# teensyShield1_0.net
KiCad netlist of a schematic drawn in EAGLE
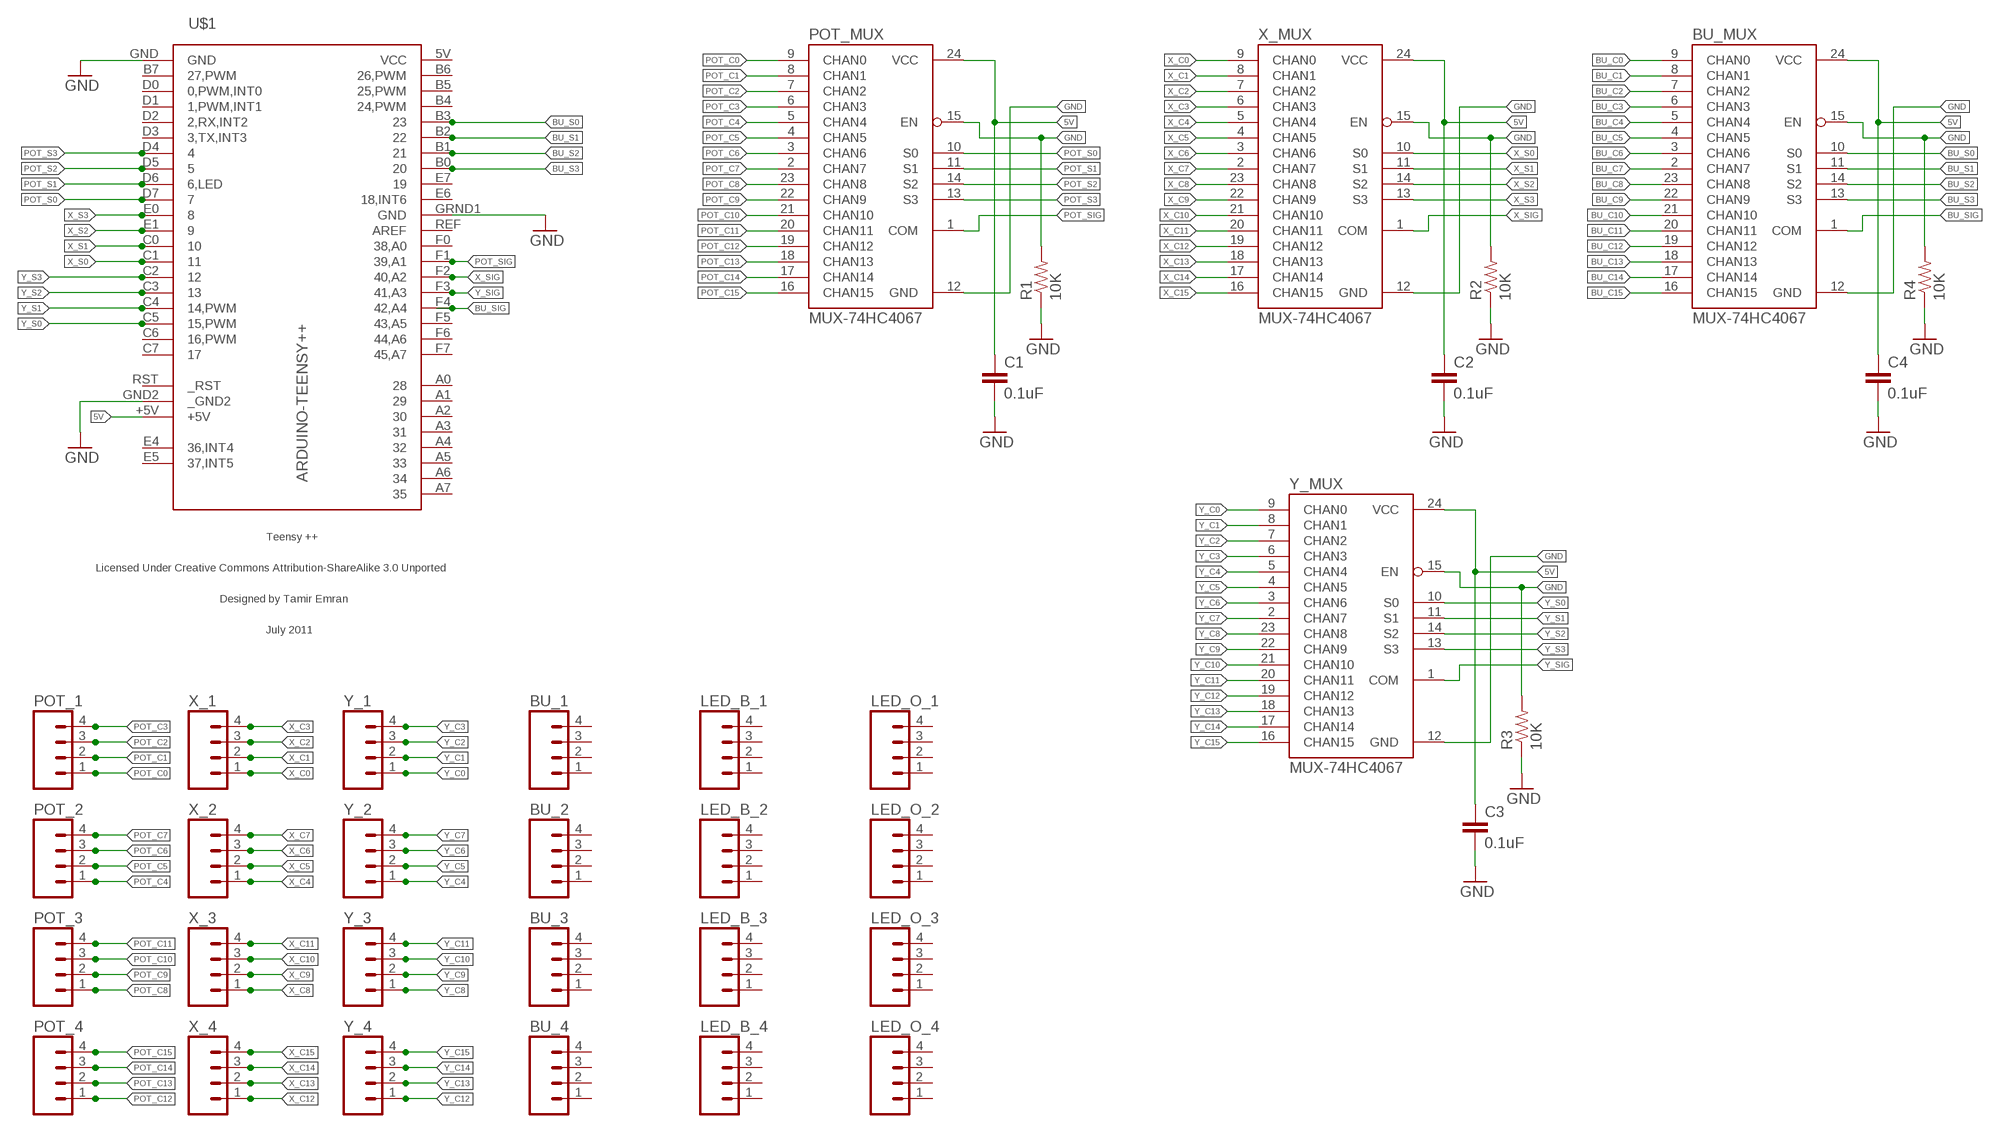
[diagram p0: schematic, sheet 1]

(export (version "E")
  (design (tool "Eeschema 10.0.6"))
  (components
    (comp (ref "BU_1")
      (value "M04NO_SILK_ALL_ROUND")
      (footprint "eagle-import:1X04_NO_SILK_ALL_ROUND")
      (libsource (lib "eagle-import") (part "M04NO_SILK_ALL_ROUND"))
    )
    (comp (ref "BU_2")
      (value "M04NO_SILK_ALL_ROUND")
      (footprint "eagle-import:1X04_NO_SILK_ALL_ROUND")
      (libsource (lib "eagle-import") (part "M04NO_SILK_ALL_ROUND"))
    )
    (comp (ref "BU_3")
      (value "M04NO_SILK_ALL_ROUND")
      (footprint "eagle-import:1X04_NO_SILK_ALL_ROUND")
      (libsource (lib "eagle-import") (part "M04NO_SILK_ALL_ROUND"))
    )
    (comp (ref "BU_4")
      (value "M04NO_SILK_ALL_ROUND")
      (footprint "eagle-import:1X04_NO_SILK_ALL_ROUND")
      (libsource (lib "eagle-import") (part "M04NO_SILK_ALL_ROUND"))
    )
    (comp (ref "BU_MUX")
      (value "MUX-74HC4067")
      (footprint "eagle-import:SSOP24")
      (libsource (lib "eagle-import") (part "MUX-74HC4067SMD"))
    )
    (comp (ref "C1")
      (value "0.1uF")
      (footprint "eagle-import:0603")
      (libsource (lib "eagle-import") (part "CAP0603"))
    )
    (comp (ref "C2")
      (value "0.1uF")
      (footprint "eagle-import:0603")
      (libsource (lib "eagle-import") (part "CAP0603"))
    )
    (comp (ref "C3")
      (value "0.1uF")
      (footprint "eagle-import:0603")
      (libsource (lib "eagle-import") (part "CAP0603"))
    )
    (comp (ref "C4")
      (value "0.1uF")
      (footprint "eagle-import:0603")
      (libsource (lib "eagle-import") (part "CAP0603"))
    )
    (comp (ref "LED_B_1")
      (value "M04NO_SILK_ALL_ROUND")
      (footprint "eagle-import:1X04_NO_SILK_ALL_ROUND")
      (libsource (lib "eagle-import") (part "M04NO_SILK_ALL_ROUND"))
    )
    (comp (ref "LED_B_2")
      (value "M04NO_SILK_ALL_ROUND")
      (footprint "eagle-import:1X04_NO_SILK_ALL_ROUND")
      (libsource (lib "eagle-import") (part "M04NO_SILK_ALL_ROUND"))
    )
    (comp (ref "LED_B_3")
      (value "M04NO_SILK_ALL_ROUND")
      (footprint "eagle-import:1X04_NO_SILK_ALL_ROUND")
      (libsource (lib "eagle-import") (part "M04NO_SILK_ALL_ROUND"))
    )
    (comp (ref "LED_B_4")
      (value "M04NO_SILK_ALL_ROUND")
      (footprint "eagle-import:1X04_NO_SILK_ALL_ROUND")
      (libsource (lib "eagle-import") (part "M04NO_SILK_ALL_ROUND"))
    )
    (comp (ref "LED_O_1")
      (value "M04NO_SILK_ALL_ROUND")
      (footprint "eagle-import:1X04_NO_SILK_ALL_ROUND")
      (libsource (lib "eagle-import") (part "M04NO_SILK_ALL_ROUND"))
    )
    (comp (ref "LED_O_2")
      (value "M04NO_SILK_ALL_ROUND")
      (footprint "eagle-import:1X04_NO_SILK_ALL_ROUND")
      (libsource (lib "eagle-import") (part "M04NO_SILK_ALL_ROUND"))
    )
    (comp (ref "LED_O_3")
      (value "M04NO_SILK_ALL_ROUND")
      (footprint "eagle-import:1X04_NO_SILK_ALL_ROUND")
      (libsource (lib "eagle-import") (part "M04NO_SILK_ALL_ROUND"))
    )
    (comp (ref "LED_O_4")
      (value "M04NO_SILK_ALL_ROUND")
      (footprint "eagle-import:1X04_NO_SILK_ALL_ROUND")
      (libsource (lib "eagle-import") (part "M04NO_SILK_ALL_ROUND"))
    )
    (comp (ref "POT_1")
      (value "M04NO_SILK_ALL_ROUND")
      (footprint "eagle-import:1X04_NO_SILK_ALL_ROUND")
      (libsource (lib "eagle-import") (part "M04NO_SILK_ALL_ROUND"))
    )
    (comp (ref "POT_2")
      (value "M04NO_SILK_ALL_ROUND")
      (footprint "eagle-import:1X04_NO_SILK_ALL_ROUND")
      (libsource (lib "eagle-import") (part "M04NO_SILK_ALL_ROUND"))
    )
    (comp (ref "POT_3")
      (value "M04NO_SILK_ALL_ROUND")
      (footprint "eagle-import:1X04_NO_SILK_ALL_ROUND")
      (libsource (lib "eagle-import") (part "M04NO_SILK_ALL_ROUND"))
    )
    (comp (ref "POT_4")
      (value "M04NO_SILK_ALL_ROUND")
      (footprint "eagle-import:1X04_NO_SILK_ALL_ROUND")
      (libsource (lib "eagle-import") (part "M04NO_SILK_ALL_ROUND"))
    )
    (comp (ref "POT_MUX")
      (value "MUX-74HC4067")
      (footprint "eagle-import:SSOP24")
      (libsource (lib "eagle-import") (part "MUX-74HC4067SMD"))
    )
    (comp (ref "R1")
      (value "10K")
      (footprint "eagle-import:0603")
      (libsource (lib "eagle-import") (part "RESISTOR0603"))
    )
    (comp (ref "R2")
      (value "10K")
      (footprint "eagle-import:0603")
      (libsource (lib "eagle-import") (part "RESISTOR0603"))
    )
    (comp (ref "R3")
      (value "10K")
      (footprint "eagle-import:0603")
      (libsource (lib "eagle-import") (part "RESISTOR0603"))
    )
    (comp (ref "R4")
      (value "10K")
      (footprint "eagle-import:0603")
      (libsource (lib "eagle-import") (part "RESISTOR0603"))
    )
    (comp (ref "U$1")
      (value "ARDUINO-TEENSY++")
      (footprint "eagle-import:TEENSY++")
      (libsource (lib "eagle-import") (part "ARDUINO-TEENSY++"))
    )
    (comp (ref "X_1")
      (value "M04NO_SILK_ALL_ROUND")
      (footprint "eagle-import:1X04_NO_SILK_ALL_ROUND")
      (libsource (lib "eagle-import") (part "M04NO_SILK_ALL_ROUND"))
    )
    (comp (ref "X_2")
      (value "M04NO_SILK_ALL_ROUND")
      (footprint "eagle-import:1X04_NO_SILK_ALL_ROUND")
      (libsource (lib "eagle-import") (part "M04NO_SILK_ALL_ROUND"))
    )
    (comp (ref "X_3")
      (value "M04NO_SILK_ALL_ROUND")
      (footprint "eagle-import:1X04_NO_SILK_ALL_ROUND")
      (libsource (lib "eagle-import") (part "M04NO_SILK_ALL_ROUND"))
    )
    (comp (ref "X_4")
      (value "M04NO_SILK_ALL_ROUND")
      (footprint "eagle-import:1X04_NO_SILK_ALL_ROUND")
      (libsource (lib "eagle-import") (part "M04NO_SILK_ALL_ROUND"))
    )
    (comp (ref "X_MUX")
      (value "MUX-74HC4067")
      (footprint "eagle-import:SSOP24")
      (libsource (lib "eagle-import") (part "MUX-74HC4067SMD"))
    )
    (comp (ref "Y_1")
      (value "M04NO_SILK_ALL_ROUND")
      (footprint "eagle-import:1X04_NO_SILK_ALL_ROUND")
      (libsource (lib "eagle-import") (part "M04NO_SILK_ALL_ROUND"))
    )
    (comp (ref "Y_2")
      (value "M04NO_SILK_ALL_ROUND")
      (footprint "eagle-import:1X04_NO_SILK_ALL_ROUND")
      (libsource (lib "eagle-import") (part "M04NO_SILK_ALL_ROUND"))
    )
    (comp (ref "Y_3")
      (value "M04NO_SILK_ALL_ROUND")
      (footprint "eagle-import:1X04_NO_SILK_ALL_ROUND")
      (libsource (lib "eagle-import") (part "M04NO_SILK_ALL_ROUND"))
    )
    (comp (ref "Y_4")
      (value "M04NO_SILK_ALL_ROUND")
      (footprint "eagle-import:1X04_NO_SILK_ALL_ROUND")
      (libsource (lib "eagle-import") (part "M04NO_SILK_ALL_ROUND"))
    )
    (comp (ref "Y_MUX")
      (value "MUX-74HC4067")
      (footprint "eagle-import:SSOP24")
      (libsource (lib "eagle-import") (part "MUX-74HC4067SMD"))
    )
  )
  (nets
    (net (code "1") (name "/VCC") (class "Default")
      (node (ref "U$1") (pin "5V") (pinfunction "VCC_5V") (pintype "power_in"))
    )
    (net (code "2") (name "5V") (class "Default")
      (node (ref "BU_MUX") (pin "24") (pinfunction "VCC_24") (pintype "bidirectional"))
      (node (ref "C1") (pin "1") (pinfunction "1_1") (pintype "passive"))
      (node (ref "C2") (pin "1") (pinfunction "1_1") (pintype "passive"))
      (node (ref "C3") (pin "1") (pinfunction "1_1") (pintype "passive"))
      (node (ref "C4") (pin "1") (pinfunction "1_1") (pintype "passive"))
      (node (ref "POT_MUX") (pin "24") (pinfunction "VCC_24") (pintype "bidirectional"))
      (node (ref "X_MUX") (pin "24") (pinfunction "VCC_24") (pintype "bidirectional"))
      (node (ref "Y_MUX") (pin "24") (pinfunction "VCC_24") (pintype "bidirectional"))
    )
    (net (code "3") (name "BU_C0") (class "Default")
      (node (ref "BU_MUX") (pin "9") (pinfunction "CHAN0_9") (pintype "bidirectional"))
    )
    (net (code "4") (name "BU_C1") (class "Default")
      (node (ref "BU_MUX") (pin "8") (pinfunction "CHAN1_8") (pintype "bidirectional"))
    )
    (net (code "5") (name "BU_C2") (class "Default")
      (node (ref "BU_MUX") (pin "7") (pinfunction "CHAN2_7") (pintype "bidirectional"))
    )
    (net (code "6") (name "BU_C3") (class "Default")
      (node (ref "BU_MUX") (pin "6") (pinfunction "CHAN3_6") (pintype "bidirectional"))
    )
    (net (code "7") (name "BU_C4") (class "Default")
      (node (ref "BU_MUX") (pin "5") (pinfunction "CHAN4_5") (pintype "bidirectional"))
    )
    (net (code "8") (name "BU_C5") (class "Default")
      (node (ref "BU_MUX") (pin "4") (pinfunction "CHAN5_4") (pintype "bidirectional"))
    )
    (net (code "9") (name "BU_C6") (class "Default")
      (node (ref "BU_MUX") (pin "3") (pinfunction "CHAN6_3") (pintype "bidirectional"))
    )
    (net (code "10") (name "BU_C7") (class "Default")
      (node (ref "BU_MUX") (pin "2") (pinfunction "CHAN7_2") (pintype "bidirectional"))
    )
    (net (code "11") (name "BU_C8") (class "Default")
      (node (ref "BU_MUX") (pin "23") (pinfunction "CHAN8_23") (pintype "bidirectional"))
    )
    (net (code "12") (name "BU_C9") (class "Default")
      (node (ref "BU_MUX") (pin "22") (pinfunction "CHAN9_22") (pintype "bidirectional"))
    )
    (net (code "13") (name "BU_C10") (class "Default")
      (node (ref "BU_MUX") (pin "21") (pinfunction "CHAN10_21") (pintype "bidirectional"))
    )
    (net (code "14") (name "BU_C11") (class "Default")
      (node (ref "BU_MUX") (pin "20") (pinfunction "CHAN11_20") (pintype "bidirectional"))
    )
    (net (code "15") (name "BU_C12") (class "Default")
      (node (ref "BU_MUX") (pin "19") (pinfunction "CHAN12_19") (pintype "bidirectional"))
    )
    (net (code "16") (name "BU_C13") (class "Default")
      (node (ref "BU_MUX") (pin "18") (pinfunction "CHAN13_18") (pintype "bidirectional"))
    )
    (net (code "17") (name "BU_C14") (class "Default")
      (node (ref "BU_MUX") (pin "17") (pinfunction "CHAN14_17") (pintype "bidirectional"))
    )
    (net (code "18") (name "BU_C15") (class "Default")
      (node (ref "BU_MUX") (pin "16") (pinfunction "CHAN15_16") (pintype "bidirectional"))
    )
    (net (code "19") (name "BU_S0") (class "Default")
      (node (ref "BU_MUX") (pin "10") (pinfunction "S0_10") (pintype "input"))
      (node (ref "U$1") (pin "B3") (pinfunction "23_B3") (pintype "bidirectional"))
    )
    (net (code "20") (name "BU_S1") (class "Default")
      (node (ref "BU_MUX") (pin "11") (pinfunction "S1_11") (pintype "input"))
      (node (ref "U$1") (pin "B2") (pinfunction "22_B2") (pintype "bidirectional"))
    )
    (net (code "21") (name "BU_S2") (class "Default")
      (node (ref "BU_MUX") (pin "14") (pinfunction "S2_14") (pintype "input"))
      (node (ref "U$1") (pin "B1") (pinfunction "21_B1") (pintype "bidirectional"))
    )
    (net (code "22") (name "BU_S3") (class "Default")
      (node (ref "BU_MUX") (pin "13") (pinfunction "S3_13") (pintype "input"))
      (node (ref "U$1") (pin "B0") (pinfunction "20_B0") (pintype "bidirectional"))
    )
    (net (code "23") (name "BU_SIG") (class "Default")
      (node (ref "BU_MUX") (pin "1") (pinfunction "COM_1") (pintype "bidirectional"))
      (node (ref "U$1") (pin "F4") (pinfunction "42,A4_F4") (pintype "bidirectional"))
    )
    (net (code "24") (name "GND") (class "Default")
      (node (ref "BU_MUX") (pin "12") (pinfunction "GND_12") (pintype "bidirectional"))
      (node (ref "BU_MUX") (pin "15") (pinfunction "EN_15") (pintype "input"))
      (node (ref "C1") (pin "2") (pinfunction "2_2") (pintype "passive"))
      (node (ref "C2") (pin "2") (pinfunction "2_2") (pintype "passive"))
      (node (ref "C3") (pin "2") (pinfunction "2_2") (pintype "passive"))
      (node (ref "C4") (pin "2") (pinfunction "2_2") (pintype "passive"))
      (node (ref "POT_MUX") (pin "12") (pinfunction "GND_12") (pintype "bidirectional"))
      (node (ref "POT_MUX") (pin "15") (pinfunction "EN_15") (pintype "input"))
      (node (ref "R1") (pin "1") (pinfunction "1_1") (pintype "passive"))
      (node (ref "R1") (pin "2") (pinfunction "2_2") (pintype "passive"))
      (node (ref "R2") (pin "1") (pinfunction "1_1") (pintype "passive"))
      (node (ref "R2") (pin "2") (pinfunction "2_2") (pintype "passive"))
      (node (ref "R3") (pin "1") (pinfunction "1_1") (pintype "passive"))
      (node (ref "R3") (pin "2") (pinfunction "2_2") (pintype "passive"))
      (node (ref "R4") (pin "1") (pinfunction "1_1") (pintype "passive"))
      (node (ref "R4") (pin "2") (pinfunction "2_2") (pintype "passive"))
      (node (ref "U$1") (pin "GND") (pinfunction "GND_GND") (pintype "power_in"))
      (node (ref "U$1") (pin "GND2") (pinfunction "_GND2_GND2") (pintype "power_in"))
      (node (ref "U$1") (pin "GRND1") (pinfunction "GND_GRND1") (pintype "power_in"))
      (node (ref "X_MUX") (pin "12") (pinfunction "GND_12") (pintype "bidirectional"))
      (node (ref "X_MUX") (pin "15") (pinfunction "EN_15") (pintype "input"))
      (node (ref "Y_MUX") (pin "12") (pinfunction "GND_12") (pintype "bidirectional"))
      (node (ref "Y_MUX") (pin "15") (pinfunction "EN_15") (pintype "input"))
    )
    (net (code "25") (name "POT_C0") (class "Default")
      (node (ref "POT_1") (pin "1") (pinfunction "1_1") (pintype "passive"))
      (node (ref "POT_MUX") (pin "9") (pinfunction "CHAN0_9") (pintype "bidirectional"))
    )
    (net (code "26") (name "POT_C1") (class "Default")
      (node (ref "POT_1") (pin "2") (pinfunction "2_2") (pintype "passive"))
      (node (ref "POT_MUX") (pin "8") (pinfunction "CHAN1_8") (pintype "bidirectional"))
    )
    (net (code "27") (name "POT_C2") (class "Default")
      (node (ref "POT_1") (pin "3") (pinfunction "3_3") (pintype "passive"))
      (node (ref "POT_MUX") (pin "7") (pinfunction "CHAN2_7") (pintype "bidirectional"))
    )
    (net (code "28") (name "POT_C3") (class "Default")
      (node (ref "POT_1") (pin "4") (pinfunction "4_4") (pintype "passive"))
      (node (ref "POT_MUX") (pin "6") (pinfunction "CHAN3_6") (pintype "bidirectional"))
    )
    (net (code "29") (name "POT_C4") (class "Default")
      (node (ref "POT_2") (pin "1") (pinfunction "1_1") (pintype "passive"))
      (node (ref "POT_MUX") (pin "5") (pinfunction "CHAN4_5") (pintype "bidirectional"))
    )
    (net (code "30") (name "POT_C5") (class "Default")
      (node (ref "POT_2") (pin "2") (pinfunction "2_2") (pintype "passive"))
      (node (ref "POT_MUX") (pin "4") (pinfunction "CHAN5_4") (pintype "bidirectional"))
    )
    (net (code "31") (name "POT_C6") (class "Default")
      (node (ref "POT_2") (pin "3") (pinfunction "3_3") (pintype "passive"))
      (node (ref "POT_MUX") (pin "3") (pinfunction "CHAN6_3") (pintype "bidirectional"))
    )
    (net (code "32") (name "POT_C7") (class "Default")
      (node (ref "POT_2") (pin "4") (pinfunction "4_4") (pintype "passive"))
      (node (ref "POT_MUX") (pin "2") (pinfunction "CHAN7_2") (pintype "bidirectional"))
    )
    (net (code "33") (name "POT_C8") (class "Default")
      (node (ref "POT_3") (pin "1") (pinfunction "1_1") (pintype "passive"))
      (node (ref "POT_MUX") (pin "23") (pinfunction "CHAN8_23") (pintype "bidirectional"))
    )
    (net (code "34") (name "POT_C9") (class "Default")
      (node (ref "POT_3") (pin "2") (pinfunction "2_2") (pintype "passive"))
      (node (ref "POT_MUX") (pin "22") (pinfunction "CHAN9_22") (pintype "bidirectional"))
    )
    (net (code "35") (name "POT_C10") (class "Default")
      (node (ref "POT_3") (pin "3") (pinfunction "3_3") (pintype "passive"))
      (node (ref "POT_MUX") (pin "21") (pinfunction "CHAN10_21") (pintype "bidirectional"))
    )
    (net (code "36") (name "POT_C11") (class "Default")
      (node (ref "POT_3") (pin "4") (pinfunction "4_4") (pintype "passive"))
      (node (ref "POT_MUX") (pin "20") (pinfunction "CHAN11_20") (pintype "bidirectional"))
    )
    (net (code "37") (name "POT_C12") (class "Default")
      (node (ref "POT_4") (pin "1") (pinfunction "1_1") (pintype "passive"))
      (node (ref "POT_MUX") (pin "19") (pinfunction "CHAN12_19") (pintype "bidirectional"))
    )
    (net (code "38") (name "POT_C13") (class "Default")
      (node (ref "POT_4") (pin "2") (pinfunction "2_2") (pintype "passive"))
      (node (ref "POT_MUX") (pin "18") (pinfunction "CHAN13_18") (pintype "bidirectional"))
    )
    (net (code "39") (name "POT_C14") (class "Default")
      (node (ref "POT_4") (pin "3") (pinfunction "3_3") (pintype "passive"))
      (node (ref "POT_MUX") (pin "17") (pinfunction "CHAN14_17") (pintype "bidirectional"))
    )
    (net (code "40") (name "POT_C15") (class "Default")
      (node (ref "POT_4") (pin "4") (pinfunction "4_4") (pintype "passive"))
      (node (ref "POT_MUX") (pin "16") (pinfunction "CHAN15_16") (pintype "bidirectional"))
    )
    (net (code "41") (name "POT_S0") (class "Default")
      (node (ref "POT_MUX") (pin "10") (pinfunction "S0_10") (pintype "input"))
      (node (ref "U$1") (pin "D7") (pinfunction "7_D7") (pintype "bidirectional"))
    )
    (net (code "42") (name "POT_S1") (class "Default")
      (node (ref "POT_MUX") (pin "11") (pinfunction "S1_11") (pintype "input"))
      (node (ref "U$1") (pin "D6") (pinfunction "6,LED_D6") (pintype "bidirectional"))
    )
    (net (code "43") (name "POT_S2") (class "Default")
      (node (ref "POT_MUX") (pin "14") (pinfunction "S2_14") (pintype "input"))
      (node (ref "U$1") (pin "D5") (pinfunction "5_D5") (pintype "bidirectional"))
    )
    (net (code "44") (name "POT_S3") (class "Default")
      (node (ref "POT_MUX") (pin "13") (pinfunction "S3_13") (pintype "input"))
      (node (ref "U$1") (pin "D4") (pinfunction "4_D4") (pintype "bidirectional"))
    )
    (net (code "45") (name "POT_SIG") (class "Default")
      (node (ref "POT_MUX") (pin "1") (pinfunction "COM_1") (pintype "bidirectional"))
    )
    (net (code "46") (name "X_C0") (class "Default")
      (node (ref "X_1") (pin "1") (pinfunction "1_1") (pintype "passive"))
      (node (ref "X_MUX") (pin "9") (pinfunction "CHAN0_9") (pintype "bidirectional"))
    )
    (net (code "47") (name "X_C1") (class "Default")
      (node (ref "X_1") (pin "2") (pinfunction "2_2") (pintype "passive"))
      (node (ref "X_MUX") (pin "8") (pinfunction "CHAN1_8") (pintype "bidirectional"))
    )
    (net (code "48") (name "X_C2") (class "Default")
      (node (ref "X_1") (pin "3") (pinfunction "3_3") (pintype "passive"))
      (node (ref "X_MUX") (pin "7") (pinfunction "CHAN2_7") (pintype "bidirectional"))
    )
    (net (code "49") (name "X_C3") (class "Default")
      (node (ref "X_1") (pin "4") (pinfunction "4_4") (pintype "passive"))
      (node (ref "X_MUX") (pin "6") (pinfunction "CHAN3_6") (pintype "bidirectional"))
    )
    (net (code "50") (name "X_C4") (class "Default")
      (node (ref "X_2") (pin "1") (pinfunction "1_1") (pintype "passive"))
      (node (ref "X_MUX") (pin "5") (pinfunction "CHAN4_5") (pintype "bidirectional"))
    )
    (net (code "51") (name "X_C5") (class "Default")
      (node (ref "X_2") (pin "2") (pinfunction "2_2") (pintype "passive"))
      (node (ref "X_MUX") (pin "4") (pinfunction "CHAN5_4") (pintype "bidirectional"))
    )
    (net (code "52") (name "X_C6") (class "Default")
      (node (ref "X_2") (pin "3") (pinfunction "3_3") (pintype "passive"))
      (node (ref "X_MUX") (pin "3") (pinfunction "CHAN6_3") (pintype "bidirectional"))
    )
    (net (code "53") (name "X_C7") (class "Default")
      (node (ref "X_2") (pin "4") (pinfunction "4_4") (pintype "passive"))
      (node (ref "X_MUX") (pin "2") (pinfunction "CHAN7_2") (pintype "bidirectional"))
    )
    (net (code "54") (name "X_C8") (class "Default")
      (node (ref "X_3") (pin "1") (pinfunction "1_1") (pintype "passive"))
      (node (ref "X_MUX") (pin "23") (pinfunction "CHAN8_23") (pintype "bidirectional"))
    )
    (net (code "55") (name "X_C9") (class "Default")
      (node (ref "X_3") (pin "2") (pinfunction "2_2") (pintype "passive"))
      (node (ref "X_MUX") (pin "22") (pinfunction "CHAN9_22") (pintype "bidirectional"))
    )
    (net (code "56") (name "X_C10") (class "Default")
      (node (ref "X_3") (pin "3") (pinfunction "3_3") (pintype "passive"))
      (node (ref "X_MUX") (pin "21") (pinfunction "CHAN10_21") (pintype "bidirectional"))
    )
    (net (code "57") (name "X_C11") (class "Default")
      (node (ref "X_3") (pin "4") (pinfunction "4_4") (pintype "passive"))
      (node (ref "X_MUX") (pin "20") (pinfunction "CHAN11_20") (pintype "bidirectional"))
    )
    (net (code "58") (name "X_C12") (class "Default")
      (node (ref "X_4") (pin "1") (pinfunction "1_1") (pintype "passive"))
      (node (ref "X_MUX") (pin "19") (pinfunction "CHAN12_19") (pintype "bidirectional"))
    )
    (net (code "59") (name "X_C13") (class "Default")
      (node (ref "X_4") (pin "2") (pinfunction "2_2") (pintype "passive"))
      (node (ref "X_MUX") (pin "18") (pinfunction "CHAN13_18") (pintype "bidirectional"))
    )
    (net (code "60") (name "X_C14") (class "Default")
      (node (ref "X_4") (pin "3") (pinfunction "3_3") (pintype "passive"))
      (node (ref "X_MUX") (pin "17") (pinfunction "CHAN14_17") (pintype "bidirectional"))
    )
    (net (code "61") (name "X_C15") (class "Default")
      (node (ref "X_4") (pin "4") (pinfunction "4_4") (pintype "passive"))
      (node (ref "X_MUX") (pin "16") (pinfunction "CHAN15_16") (pintype "bidirectional"))
    )
    (net (code "62") (name "X_S0") (class "Default")
      (node (ref "U$1") (pin "C1") (pinfunction "11_C1") (pintype "bidirectional"))
      (node (ref "X_MUX") (pin "10") (pinfunction "S0_10") (pintype "input"))
    )
    (net (code "63") (name "X_S1") (class "Default")
      (node (ref "U$1") (pin "C0") (pinfunction "10_C0") (pintype "bidirectional"))
      (node (ref "X_MUX") (pin "11") (pinfunction "S1_11") (pintype "input"))
    )
    (net (code "64") (name "X_S2") (class "Default")
      (node (ref "U$1") (pin "E1") (pinfunction "9_E1") (pintype "bidirectional"))
      (node (ref "X_MUX") (pin "14") (pinfunction "S2_14") (pintype "input"))
    )
    (net (code "65") (name "X_S3") (class "Default")
      (node (ref "U$1") (pin "E0") (pinfunction "8_E0") (pintype "bidirectional"))
      (node (ref "X_MUX") (pin "13") (pinfunction "S3_13") (pintype "input"))
    )
    (net (code "66") (name "X_SIG") (class "Default")
      (node (ref "X_MUX") (pin "1") (pinfunction "COM_1") (pintype "bidirectional"))
    )
    (net (code "67") (name "Y_C0") (class "Default")
      (node (ref "Y_1") (pin "1") (pinfunction "1_1") (pintype "passive"))
      (node (ref "Y_MUX") (pin "9") (pinfunction "CHAN0_9") (pintype "bidirectional"))
    )
    (net (code "68") (name "Y_C1") (class "Default")
      (node (ref "Y_1") (pin "2") (pinfunction "2_2") (pintype "passive"))
      (node (ref "Y_MUX") (pin "8") (pinfunction "CHAN1_8") (pintype "bidirectional"))
    )
    (net (code "69") (name "Y_C2") (class "Default")
      (node (ref "Y_1") (pin "3") (pinfunction "3_3") (pintype "passive"))
      (node (ref "Y_MUX") (pin "7") (pinfunction "CHAN2_7") (pintype "bidirectional"))
    )
    (net (code "70") (name "Y_C3") (class "Default")
      (node (ref "Y_1") (pin "4") (pinfunction "4_4") (pintype "passive"))
      (node (ref "Y_MUX") (pin "6") (pinfunction "CHAN3_6") (pintype "bidirectional"))
    )
    (net (code "71") (name "Y_C4") (class "Default")
      (node (ref "Y_2") (pin "1") (pinfunction "1_1") (pintype "passive"))
      (node (ref "Y_MUX") (pin "5") (pinfunction "CHAN4_5") (pintype "bidirectional"))
    )
    (net (code "72") (name "Y_C5") (class "Default")
      (node (ref "Y_2") (pin "2") (pinfunction "2_2") (pintype "passive"))
      (node (ref "Y_MUX") (pin "4") (pinfunction "CHAN5_4") (pintype "bidirectional"))
    )
    (net (code "73") (name "Y_C6") (class "Default")
      (node (ref "Y_2") (pin "3") (pinfunction "3_3") (pintype "passive"))
      (node (ref "Y_MUX") (pin "3") (pinfunction "CHAN6_3") (pintype "bidirectional"))
    )
    (net (code "74") (name "Y_C7") (class "Default")
      (node (ref "Y_2") (pin "4") (pinfunction "4_4") (pintype "passive"))
      (node (ref "Y_MUX") (pin "2") (pinfunction "CHAN7_2") (pintype "bidirectional"))
    )
    (net (code "75") (name "Y_C8") (class "Default")
      (node (ref "Y_3") (pin "1") (pinfunction "1_1") (pintype "passive"))
      (node (ref "Y_MUX") (pin "23") (pinfunction "CHAN8_23") (pintype "bidirectional"))
    )
    (net (code "76") (name "Y_C9") (class "Default")
      (node (ref "Y_3") (pin "2") (pinfunction "2_2") (pintype "passive"))
      (node (ref "Y_MUX") (pin "22") (pinfunction "CHAN9_22") (pintype "bidirectional"))
    )
    (net (code "77") (name "Y_C10") (class "Default")
      (node (ref "Y_3") (pin "3") (pinfunction "3_3") (pintype "passive"))
      (node (ref "Y_MUX") (pin "21") (pinfunction "CHAN10_21") (pintype "bidirectional"))
    )
    (net (code "78") (name "Y_C11") (class "Default")
      (node (ref "Y_3") (pin "4") (pinfunction "4_4") (pintype "passive"))
      (node (ref "Y_MUX") (pin "20") (pinfunction "CHAN11_20") (pintype "bidirectional"))
    )
    (net (code "79") (name "Y_C12") (class "Default")
      (node (ref "Y_4") (pin "1") (pinfunction "1_1") (pintype "passive"))
      (node (ref "Y_MUX") (pin "19") (pinfunction "CHAN12_19") (pintype "bidirectional"))
    )
    (net (code "80") (name "Y_C13") (class "Default")
      (node (ref "Y_4") (pin "2") (pinfunction "2_2") (pintype "passive"))
      (node (ref "Y_MUX") (pin "18") (pinfunction "CHAN13_18") (pintype "bidirectional"))
    )
    (net (code "81") (name "Y_C14") (class "Default")
      (node (ref "Y_4") (pin "3") (pinfunction "3_3") (pintype "passive"))
      (node (ref "Y_MUX") (pin "17") (pinfunction "CHAN14_17") (pintype "bidirectional"))
    )
    (net (code "82") (name "Y_C15") (class "Default")
      (node (ref "Y_4") (pin "4") (pinfunction "4_4") (pintype "passive"))
      (node (ref "Y_MUX") (pin "16") (pinfunction "CHAN15_16") (pintype "bidirectional"))
    )
    (net (code "83") (name "Y_S0") (class "Default")
      (node (ref "U$1") (pin "C5") (pinfunction "15,PWM_C5") (pintype "bidirectional"))
      (node (ref "Y_MUX") (pin "10") (pinfunction "S0_10") (pintype "input"))
    )
    (net (code "84") (name "Y_S1") (class "Default")
      (node (ref "U$1") (pin "C4") (pinfunction "14,PWM_C4") (pintype "bidirectional"))
      (node (ref "Y_MUX") (pin "11") (pinfunction "S1_11") (pintype "input"))
    )
    (net (code "85") (name "Y_S2") (class "Default")
      (node (ref "U$1") (pin "C3") (pinfunction "13_C3") (pintype "bidirectional"))
      (node (ref "Y_MUX") (pin "14") (pinfunction "S2_14") (pintype "input"))
    )
    (net (code "86") (name "Y_S3") (class "Default")
      (node (ref "U$1") (pin "C2") (pinfunction "12_C2") (pintype "bidirectional"))
      (node (ref "Y_MUX") (pin "13") (pinfunction "S3_13") (pintype "input"))
    )
    (net (code "87") (name "Y_SIG") (class "Default")
      (node (ref "U$1") (pin "F3") (pinfunction "41,A3_F3") (pintype "bidirectional"))
      (node (ref "Y_MUX") (pin "1") (pinfunction "COM_1") (pintype "bidirectional"))
    )
    (net (code "88") (name "unconnected-(BU_1-Pad1)") (class "Default")
      (node (ref "BU_1") (pin "1") (pinfunction "1_1") (pintype "passive"))
    )
    (net (code "89") (name "unconnected-(BU_1-Pad2)") (class "Default")
      (node (ref "BU_1") (pin "2") (pinfunction "2_2") (pintype "passive"))
    )
    (net (code "90") (name "unconnected-(BU_1-Pad3)") (class "Default")
      (node (ref "BU_1") (pin "3") (pinfunction "3_3") (pintype "passive"))
    )
    (net (code "91") (name "unconnected-(BU_1-Pad4)") (class "Default")
      (node (ref "BU_1") (pin "4") (pinfunction "4_4") (pintype "passive"))
    )
    (net (code "92") (name "unconnected-(BU_2-Pad1)") (class "Default")
      (node (ref "BU_2") (pin "1") (pinfunction "1_1") (pintype "passive"))
    )
    (net (code "93") (name "unconnected-(BU_2-Pad2)") (class "Default")
      (node (ref "BU_2") (pin "2") (pinfunction "2_2") (pintype "passive"))
    )
    (net (code "94") (name "unconnected-(BU_2-Pad3)") (class "Default")
      (node (ref "BU_2") (pin "3") (pinfunction "3_3") (pintype "passive"))
    )
    (net (code "95") (name "unconnected-(BU_2-Pad4)") (class "Default")
      (node (ref "BU_2") (pin "4") (pinfunction "4_4") (pintype "passive"))
    )
    (net (code "96") (name "unconnected-(BU_3-Pad1)") (class "Default")
      (node (ref "BU_3") (pin "1") (pinfunction "1_1") (pintype "passive"))
    )
    (net (code "97") (name "unconnected-(BU_3-Pad2)") (class "Default")
      (node (ref "BU_3") (pin "2") (pinfunction "2_2") (pintype "passive"))
    )
    (net (code "98") (name "unconnected-(BU_3-Pad3)") (class "Default")
      (node (ref "BU_3") (pin "3") (pinfunction "3_3") (pintype "passive"))
    )
    (net (code "99") (name "unconnected-(BU_3-Pad4)") (class "Default")
      (node (ref "BU_3") (pin "4") (pinfunction "4_4") (pintype "passive"))
    )
    (net (code "100") (name "unconnected-(BU_4-Pad1)") (class "Default")
      (node (ref "BU_4") (pin "1") (pinfunction "1_1") (pintype "passive"))
    )
    (net (code "101") (name "unconnected-(BU_4-Pad2)") (class "Default")
      (node (ref "BU_4") (pin "2") (pinfunction "2_2") (pintype "passive"))
    )
    (net (code "102") (name "unconnected-(BU_4-Pad3)") (class "Default")
      (node (ref "BU_4") (pin "3") (pinfunction "3_3") (pintype "passive"))
    )
    (net (code "103") (name "unconnected-(BU_4-Pad4)") (class "Default")
      (node (ref "BU_4") (pin "4") (pinfunction "4_4") (pintype "passive"))
    )
    (net (code "104") (name "unconnected-(LED_B_1-Pad1)") (class "Default")
      (node (ref "LED_B_1") (pin "1") (pinfunction "1_1") (pintype "passive"))
    )
    (net (code "105") (name "unconnected-(LED_B_1-Pad2)") (class "Default")
      (node (ref "LED_B_1") (pin "2") (pinfunction "2_2") (pintype "passive"))
    )
    (net (code "106") (name "unconnected-(LED_B_1-Pad3)") (class "Default")
      (node (ref "LED_B_1") (pin "3") (pinfunction "3_3") (pintype "passive"))
    )
    (net (code "107") (name "unconnected-(LED_B_1-Pad4)") (class "Default")
      (node (ref "LED_B_1") (pin "4") (pinfunction "4_4") (pintype "passive"))
    )
    (net (code "108") (name "unconnected-(LED_B_2-Pad1)") (class "Default")
      (node (ref "LED_B_2") (pin "1") (pinfunction "1_1") (pintype "passive"))
    )
    (net (code "109") (name "unconnected-(LED_B_2-Pad2)") (class "Default")
      (node (ref "LED_B_2") (pin "2") (pinfunction "2_2") (pintype "passive"))
    )
    (net (code "110") (name "unconnected-(LED_B_2-Pad3)") (class "Default")
      (node (ref "LED_B_2") (pin "3") (pinfunction "3_3") (pintype "passive"))
    )
    (net (code "111") (name "unconnected-(LED_B_2-Pad4)") (class "Default")
      (node (ref "LED_B_2") (pin "4") (pinfunction "4_4") (pintype "passive"))
    )
    (net (code "112") (name "unconnected-(LED_B_3-Pad1)") (class "Default")
      (node (ref "LED_B_3") (pin "1") (pinfunction "1_1") (pintype "passive"))
    )
    (net (code "113") (name "unconnected-(LED_B_3-Pad2)") (class "Default")
      (node (ref "LED_B_3") (pin "2") (pinfunction "2_2") (pintype "passive"))
    )
    (net (code "114") (name "unconnected-(LED_B_3-Pad3)") (class "Default")
      (node (ref "LED_B_3") (pin "3") (pinfunction "3_3") (pintype "passive"))
    )
    (net (code "115") (name "unconnected-(LED_B_3-Pad4)") (class "Default")
      (node (ref "LED_B_3") (pin "4") (pinfunction "4_4") (pintype "passive"))
    )
    (net (code "116") (name "unconnected-(LED_B_4-Pad1)") (class "Default")
      (node (ref "LED_B_4") (pin "1") (pinfunction "1_1") (pintype "passive"))
    )
    (net (code "117") (name "unconnected-(LED_B_4-Pad2)") (class "Default")
      (node (ref "LED_B_4") (pin "2") (pinfunction "2_2") (pintype "passive"))
    )
    (net (code "118") (name "unconnected-(LED_B_4-Pad3)") (class "Default")
      (node (ref "LED_B_4") (pin "3") (pinfunction "3_3") (pintype "passive"))
    )
    (net (code "119") (name "unconnected-(LED_B_4-Pad4)") (class "Default")
      (node (ref "LED_B_4") (pin "4") (pinfunction "4_4") (pintype "passive"))
    )
    (net (code "120") (name "unconnected-(LED_O_1-Pad1)") (class "Default")
      (node (ref "LED_O_1") (pin "1") (pinfunction "1_1") (pintype "passive"))
    )
    (net (code "121") (name "unconnected-(LED_O_1-Pad2)") (class "Default")
      (node (ref "LED_O_1") (pin "2") (pinfunction "2_2") (pintype "passive"))
    )
    (net (code "122") (name "unconnected-(LED_O_1-Pad3)") (class "Default")
      (node (ref "LED_O_1") (pin "3") (pinfunction "3_3") (pintype "passive"))
    )
    (net (code "123") (name "unconnected-(LED_O_1-Pad4)") (class "Default")
      (node (ref "LED_O_1") (pin "4") (pinfunction "4_4") (pintype "passive"))
    )
    (net (code "124") (name "unconnected-(LED_O_2-Pad1)") (class "Default")
      (node (ref "LED_O_2") (pin "1") (pinfunction "1_1") (pintype "passive"))
    )
    (net (code "125") (name "unconnected-(LED_O_2-Pad2)") (class "Default")
      (node (ref "LED_O_2") (pin "2") (pinfunction "2_2") (pintype "passive"))
    )
    (net (code "126") (name "unconnected-(LED_O_2-Pad3)") (class "Default")
      (node (ref "LED_O_2") (pin "3") (pinfunction "3_3") (pintype "passive"))
    )
    (net (code "127") (name "unconnected-(LED_O_2-Pad4)") (class "Default")
      (node (ref "LED_O_2") (pin "4") (pinfunction "4_4") (pintype "passive"))
    )
    (net (code "128") (name "unconnected-(LED_O_3-Pad1)") (class "Default")
      (node (ref "LED_O_3") (pin "1") (pinfunction "1_1") (pintype "passive"))
    )
    (net (code "129") (name "unconnected-(LED_O_3-Pad2)") (class "Default")
      (node (ref "LED_O_3") (pin "2") (pinfunction "2_2") (pintype "passive"))
    )
    (net (code "130") (name "unconnected-(LED_O_3-Pad3)") (class "Default")
      (node (ref "LED_O_3") (pin "3") (pinfunction "3_3") (pintype "passive"))
    )
    (net (code "131") (name "unconnected-(LED_O_3-Pad4)") (class "Default")
      (node (ref "LED_O_3") (pin "4") (pinfunction "4_4") (pintype "passive"))
    )
    (net (code "132") (name "unconnected-(LED_O_4-Pad1)") (class "Default")
      (node (ref "LED_O_4") (pin "1") (pinfunction "1_1") (pintype "passive"))
    )
    (net (code "133") (name "unconnected-(LED_O_4-Pad2)") (class "Default")
      (node (ref "LED_O_4") (pin "2") (pinfunction "2_2") (pintype "passive"))
    )
    (net (code "134") (name "unconnected-(LED_O_4-Pad3)") (class "Default")
      (node (ref "LED_O_4") (pin "3") (pinfunction "3_3") (pintype "passive"))
    )
    (net (code "135") (name "unconnected-(LED_O_4-Pad4)") (class "Default")
      (node (ref "LED_O_4") (pin "4") (pinfunction "4_4") (pintype "passive"))
    )
    (net (code "136") (name "unconnected-(U$1-0,PWM,INT0-PadD0)") (class "Default")
      (node (ref "U$1") (pin "D0") (pinfunction "0,PWM,INT0_D0") (pintype "bidirectional"))
    )
    (net (code "137") (name "unconnected-(U$1-1,PWM,INT1-PadD1)") (class "Default")
      (node (ref "U$1") (pin "D1") (pinfunction "1,PWM,INT1_D1") (pintype "bidirectional"))
    )
    (net (code "138") (name "unconnected-(U$1-2,RX,INT2-PadD2)") (class "Default")
      (node (ref "U$1") (pin "D2") (pinfunction "2,RX,INT2_D2") (pintype "bidirectional"))
    )
    (net (code "139") (name "unconnected-(U$1-3,TX,INT3-PadD3)") (class "Default")
      (node (ref "U$1") (pin "D3") (pinfunction "3,TX,INT3_D3") (pintype "bidirectional"))
    )
    (net (code "140") (name "unconnected-(U$1-16,PWM-PadC6)") (class "Default")
      (node (ref "U$1") (pin "C6") (pinfunction "16,PWM_C6") (pintype "bidirectional"))
    )
    (net (code "141") (name "unconnected-(U$1-17-PadC7)") (class "Default")
      (node (ref "U$1") (pin "C7") (pinfunction "17_C7") (pintype "bidirectional"))
    )
    (net (code "142") (name "unconnected-(U$1-18,INT6-PadE6)") (class "Default")
      (node (ref "U$1") (pin "E6") (pinfunction "18,INT6_E6") (pintype "bidirectional"))
    )
    (net (code "143") (name "unconnected-(U$1-19-PadE7)") (class "Default")
      (node (ref "U$1") (pin "E7") (pinfunction "19_E7") (pintype "bidirectional"))
    )
    (net (code "144") (name "unconnected-(U$1-24,PWM-PadB4)") (class "Default")
      (node (ref "U$1") (pin "B4") (pinfunction "24,PWM_B4") (pintype "bidirectional"))
    )
    (net (code "145") (name "unconnected-(U$1-25,PWM-PadB5)") (class "Default")
      (node (ref "U$1") (pin "B5") (pinfunction "25,PWM_B5") (pintype "bidirectional"))
    )
    (net (code "146") (name "unconnected-(U$1-26,PWM-PadB6)") (class "Default")
      (node (ref "U$1") (pin "B6") (pinfunction "26,PWM_B6") (pintype "bidirectional"))
    )
    (net (code "147") (name "unconnected-(U$1-27,PWM-PadB7)") (class "Default")
      (node (ref "U$1") (pin "B7") (pinfunction "27,PWM_B7") (pintype "bidirectional"))
    )
    (net (code "148") (name "unconnected-(U$1-28-PadA0)") (class "Default")
      (node (ref "U$1") (pin "A0") (pinfunction "28_A0") (pintype "bidirectional"))
    )
    (net (code "149") (name "unconnected-(U$1-29-PadA1)") (class "Default")
      (node (ref "U$1") (pin "A1") (pinfunction "29_A1") (pintype "bidirectional"))
    )
    (net (code "150") (name "unconnected-(U$1-30-PadA2)") (class "Default")
      (node (ref "U$1") (pin "A2") (pinfunction "30_A2") (pintype "bidirectional"))
    )
    (net (code "151") (name "unconnected-(U$1-31-PadA3)") (class "Default")
      (node (ref "U$1") (pin "A3") (pinfunction "31_A3") (pintype "bidirectional"))
    )
    (net (code "152") (name "unconnected-(U$1-32-PadA4)") (class "Default")
      (node (ref "U$1") (pin "A4") (pinfunction "32_A4") (pintype "bidirectional"))
    )
    (net (code "153") (name "unconnected-(U$1-33-PadA5)") (class "Default")
      (node (ref "U$1") (pin "A5") (pinfunction "33_A5") (pintype "bidirectional"))
    )
    (net (code "154") (name "unconnected-(U$1-34-PadA6)") (class "Default")
      (node (ref "U$1") (pin "A6") (pinfunction "34_A6") (pintype "bidirectional"))
    )
    (net (code "155") (name "unconnected-(U$1-35-PadA7)") (class "Default")
      (node (ref "U$1") (pin "A7") (pinfunction "35_A7") (pintype "bidirectional"))
    )
    (net (code "156") (name "unconnected-(U$1-36,INT4-PadE4)") (class "Default")
      (node (ref "U$1") (pin "E4") (pinfunction "36,INT4_E4") (pintype "bidirectional"))
    )
    (net (code "157") (name "unconnected-(U$1-37,INT5-PadE5)") (class "Default")
      (node (ref "U$1") (pin "E5") (pinfunction "37,INT5_E5") (pintype "bidirectional"))
    )
    (net (code "158") (name "unconnected-(U$1-38,A0-PadF0)") (class "Default")
      (node (ref "U$1") (pin "F0") (pinfunction "38,A0_F0") (pintype "bidirectional"))
    )
    (net (code "159") (name "unconnected-(U$1-39,A1-PadF1)") (class "Default")
      (node (ref "U$1") (pin "F1") (pinfunction "39,A1_F1") (pintype "bidirectional"))
    )
    (net (code "160") (name "unconnected-(U$1-40,A2-PadF2)") (class "Default")
      (node (ref "U$1") (pin "F2") (pinfunction "40,A2_F2") (pintype "bidirectional"))
    )
    (net (code "161") (name "unconnected-(U$1-43,A5-PadF5)") (class "Default")
      (node (ref "U$1") (pin "F5") (pinfunction "43,A5_F5") (pintype "bidirectional"))
    )
    (net (code "162") (name "unconnected-(U$1-44,A6-PadF6)") (class "Default")
      (node (ref "U$1") (pin "F6") (pinfunction "44,A6_F6") (pintype "bidirectional"))
    )
    (net (code "163") (name "unconnected-(U$1-45,A7-PadF7)") (class "Default")
      (node (ref "U$1") (pin "F7") (pinfunction "45,A7_F7") (pintype "bidirectional"))
    )
    (net (code "164") (name "unconnected-(U$1-AREF-PadREF)") (class "Default")
      (node (ref "U$1") (pin "REF") (pinfunction "AREF_REF") (pintype "input"))
    )
    (net (code "165") (name "unconnected-(U$1-Pad+5V)") (class "Default")
      (node (ref "U$1") (pin "+5V") (pinfunction "+5V_+5V") (pintype "power_in"))
    )
    (net (code "166") (name "unconnected-(U$1-_RST-PadRST)") (class "Default")
      (node (ref "U$1") (pin "RST") (pinfunction "_RST_RST") (pintype "input"))
    )
  )
)
